# Wilssen_core_v0_207a.net
KiCad netlist of a schematic drawn in EAGLE
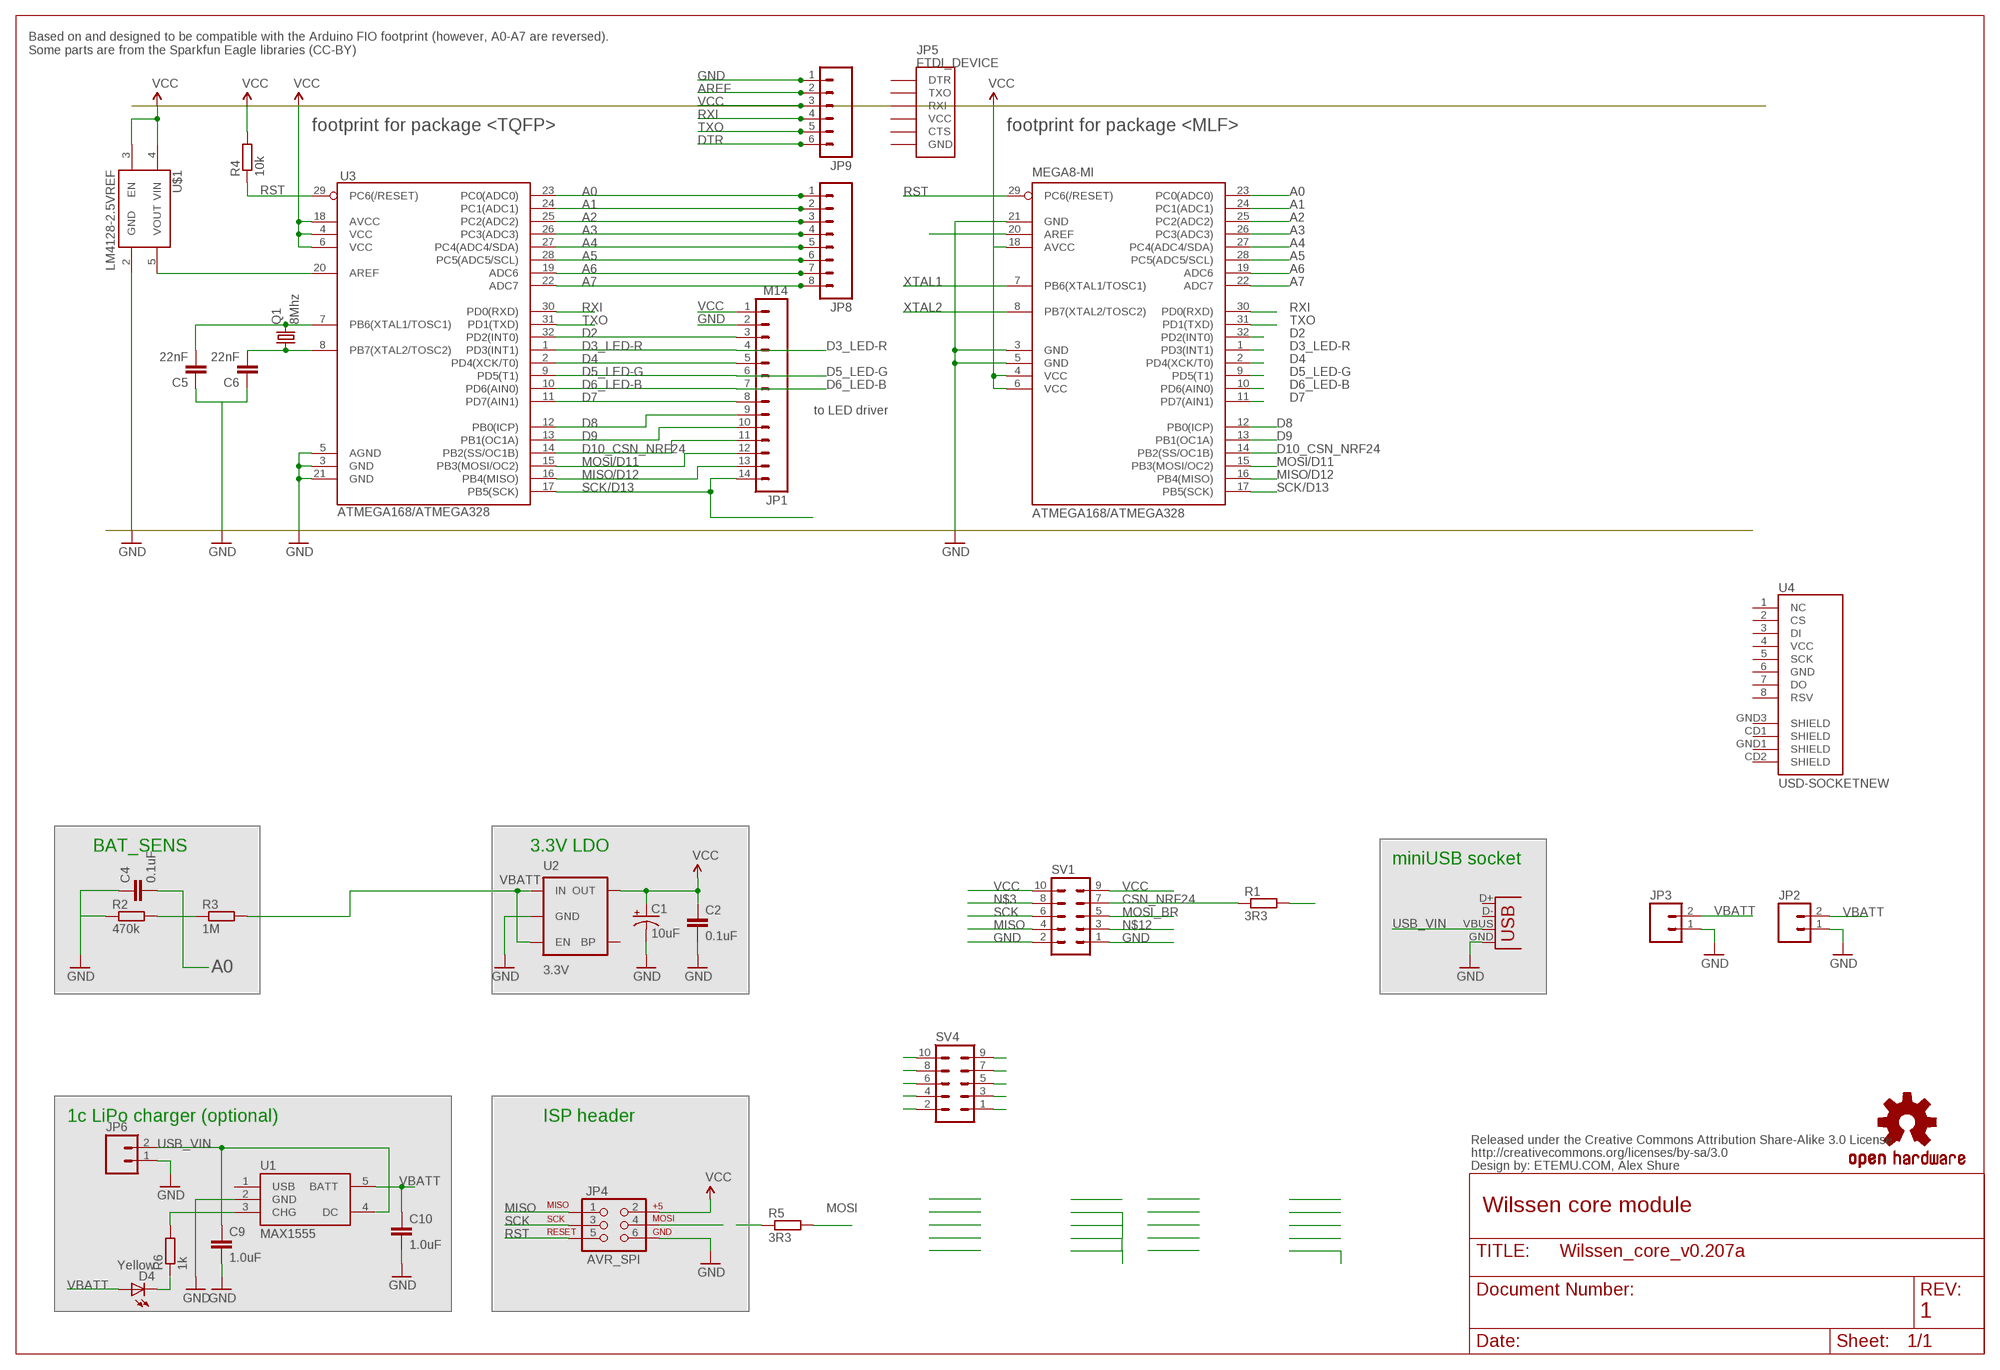
[diagram p0: schematic, sheet 1, part 1 of 2]
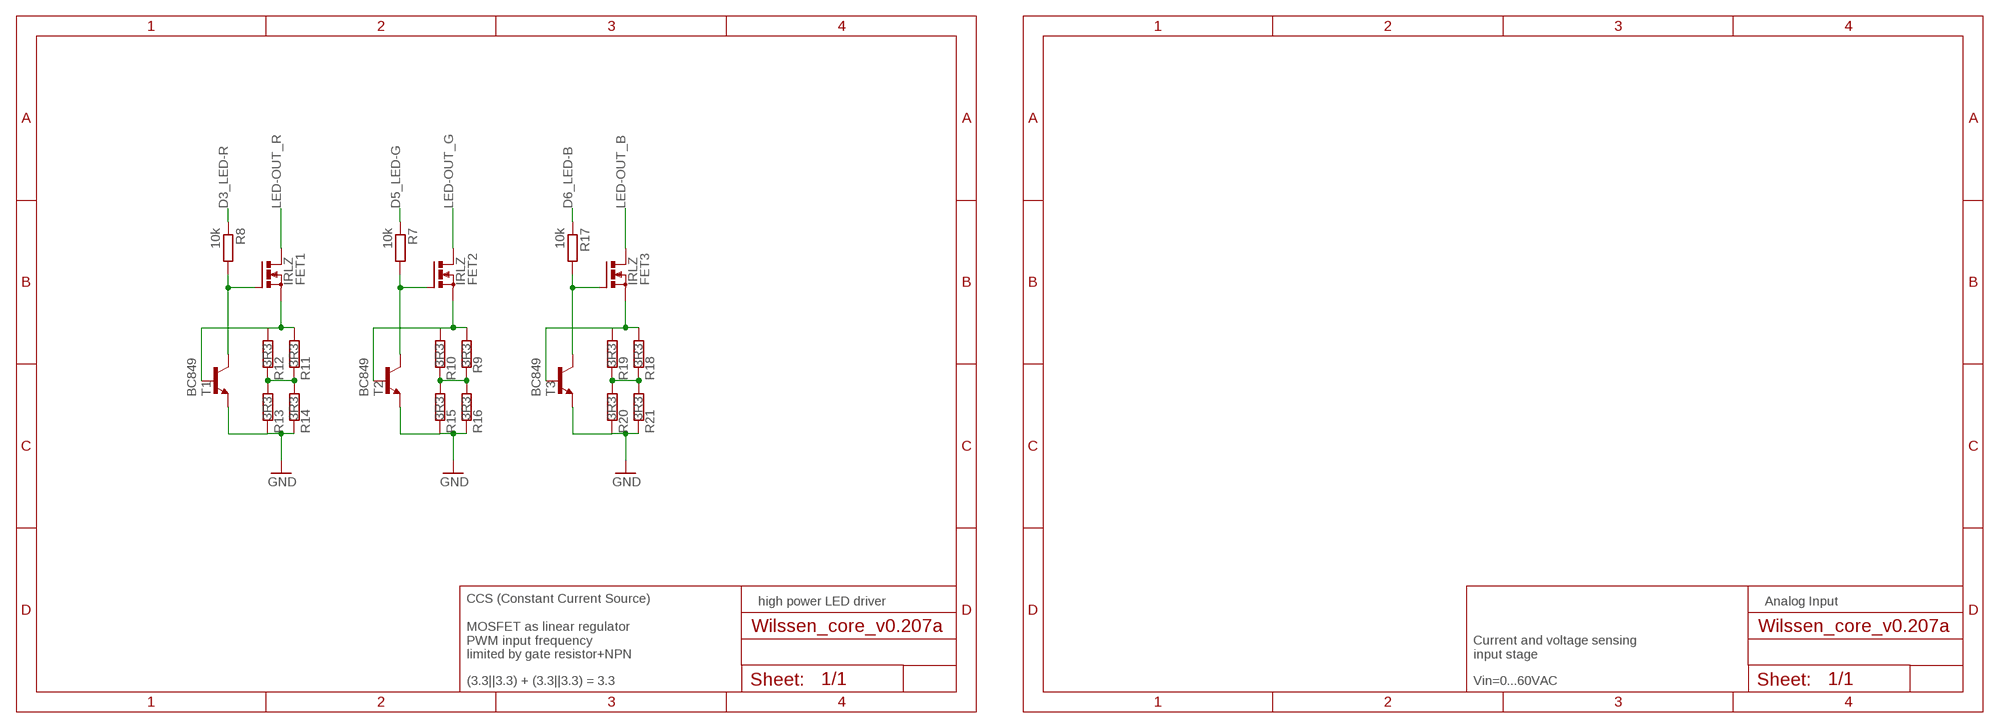
[diagram p1: schematic, sheet 1, part 2 of 2]

(export (version "E")
  (design (tool "Eeschema 10.0.6"))
  (components
    (comp (ref "ATMEGA168/ATMEGA328")
      (value "MEGA8-MI")
      (footprint "eagle-import:MLF32")
      (fields (field (name "MPN") "ATMEGA88PA-MU"))
      (libsource (lib "eagle-import") (part "MEGA8-MI"))
    )
    (comp (ref "C1")
      (value "10uF")
      (footprint "eagle-import:EIA3216")
      (libsource (lib "eagle-import") (part "CAP_POL1206"))
    )
    (comp (ref "C2")
      (value "0.1uF")
      (footprint "eagle-import:0805")
      (libsource (lib "eagle-import") (part "CAP0805"))
    )
    (comp (ref "C4")
      (value "0.1uF")
      (footprint "eagle-import:0805")
      (libsource (lib "eagle-import") (part "CAP0805"))
    )
    (comp (ref "C5")
      (value "22nF")
      (footprint "eagle-import:0805")
      (libsource (lib "eagle-import") (part "CAP0805"))
    )
    (comp (ref "C6")
      (value "22nF")
      (footprint "eagle-import:0805")
      (libsource (lib "eagle-import") (part "CAP0805"))
    )
    (comp (ref "C9")
      (value "1.0uF")
      (footprint "eagle-import:0805")
      (libsource (lib "eagle-import") (part "CAP0805"))
    )
    (comp (ref "C10")
      (value "1.0uF")
      (footprint "eagle-import:0805")
      (libsource (lib "eagle-import") (part "CAP0805"))
    )
    (comp (ref "CC_TEXT1")
      (value "CREATIVE_COMMONS")
      (footprint "eagle-import:CREATIVE_COMMONS")
      (libsource (lib "eagle-import") (part "CREATIVE_COMMONS"))
    )
    (comp (ref "D4")
      (value "Yellow")
      (footprint "eagle-import:LED-0603")
      (libsource (lib "eagle-import") (part "LED0603"))
    )
    (comp (ref "FET1")
      (value "IRLZ")
      (footprint "eagle-import:TO220BV")
      (libsource (lib "eagle-import") (part "PMOSFET_NTO220BV"))
    )
    (comp (ref "FET2")
      (value "IRLZ")
      (footprint "eagle-import:TO220BV")
      (libsource (lib "eagle-import") (part "PMOSFET_NTO220BV"))
    )
    (comp (ref "FET3")
      (value "IRLZ")
      (footprint "eagle-import:TO220BV")
      (libsource (lib "eagle-import") (part "PMOSFET_NTO220BV"))
    )
    (comp (ref "JP1")
      (value "M14")
      (footprint "eagle-import:1X14")
      (libsource (lib "eagle-import") (part "M14"))
    )
    (comp (ref "JP2")
      (value "M02PTH")
      (footprint "eagle-import:1X02")
      (libsource (lib "eagle-import") (part "M02PTH"))
    )
    (comp (ref "JP3")
      (value "M02-JST-2MM-SMT")
      (footprint "eagle-import:S2B-PH")
      (libsource (lib "eagle-import") (part "M02-JST-2MM-SMT"))
    )
    (comp (ref "JP4")
      (value "AVR_SPI")
      (footprint "eagle-import:2X3")
      (libsource (lib "eagle-import") (part "AVR_SPI_PRG_6PTH"))
    )
    (comp (ref "JP5")
      (value "FTDI_DEVICE")
      (footprint "eagle-import:FTDI_DEVICE_SIDE")
      (libsource (lib "eagle-import") (part "FTDI_DEVICE"))
    )
    (comp (ref "JP6")
      (value "M02PTH")
      (footprint "eagle-import:1X02")
      (libsource (lib "eagle-import") (part "M02PTH"))
    )
    (comp (ref "JP8")
      (value "M081X08")
      (footprint "eagle-import:1X08")
      (libsource (lib "eagle-import") (part "M081X08"))
    )
    (comp (ref "JP9")
      (value "M06SIP")
      (footprint "eagle-import:1X06")
      (libsource (lib "eagle-import") (part "M06SIP"))
    )
    (comp (ref "LOGO1")
      (value "OSHW-LOGOS")
      (footprint "eagle-import:OSHW-LOGO-S")
      (libsource (lib "eagle-import") (part "OSHW-LOGOS"))
    )
    (comp (ref "Q1")
      (value "8Mhz")
      (footprint "eagle-import:SM49")
      (libsource (lib "eagle-import") (part "CRYSTALSM49"))
    )
    (comp (ref "R1")
      (value "3R3")
      (footprint "eagle-import:R1206")
      (libsource (lib "eagle-import") (part "R-EU_R1206"))
    )
    (comp (ref "R2")
      (value "470k")
      (footprint "eagle-import:R0805")
      (libsource (lib "eagle-import") (part "R-EU_R0805"))
    )
    (comp (ref "R3")
      (value "1M")
      (footprint "eagle-import:R0805")
      (libsource (lib "eagle-import") (part "R-EU_R0805"))
    )
    (comp (ref "R4")
      (value "10k")
      (footprint "eagle-import:R0805")
      (libsource (lib "eagle-import") (part "R-EU_R0805"))
    )
    (comp (ref "R5")
      (value "3R3")
      (footprint "eagle-import:R1206")
      (libsource (lib "eagle-import") (part "R-EU_R1206"))
    )
    (comp (ref "R6")
      (value "1k")
      (footprint "eagle-import:R0805")
      (libsource (lib "eagle-import") (part "R-EU_R0805"))
    )
    (comp (ref "R7")
      (value "10k")
      (footprint "eagle-import:R0805")
      (libsource (lib "eagle-import") (part "resistor_R-EU_R0805"))
    )
    (comp (ref "R8")
      (value "10k")
      (footprint "eagle-import:R0805")
      (libsource (lib "eagle-import") (part "resistor_R-EU_R0805"))
    )
    (comp (ref "R9")
      (value "3R3")
      (footprint "eagle-import:R1206")
      (libsource (lib "eagle-import") (part "resistor_R-EU_R1206"))
    )
    (comp (ref "R10")
      (value "3R3")
      (footprint "eagle-import:R1206")
      (libsource (lib "eagle-import") (part "resistor_R-EU_R1206"))
    )
    (comp (ref "R11")
      (value "3R3")
      (footprint "eagle-import:R1206")
      (libsource (lib "eagle-import") (part "resistor_R-EU_R1206"))
    )
    (comp (ref "R12")
      (value "3R3")
      (footprint "eagle-import:R1206")
      (libsource (lib "eagle-import") (part "resistor_R-EU_R1206"))
    )
    (comp (ref "R13")
      (value "3R3")
      (footprint "eagle-import:R1206")
      (libsource (lib "eagle-import") (part "resistor_R-EU_R1206"))
    )
    (comp (ref "R14")
      (value "3R3")
      (footprint "eagle-import:R1206")
      (libsource (lib "eagle-import") (part "resistor_R-EU_R1206"))
    )
    (comp (ref "R15")
      (value "3R3")
      (footprint "eagle-import:R1206")
      (libsource (lib "eagle-import") (part "resistor_R-EU_R1206"))
    )
    (comp (ref "R16")
      (value "3R3")
      (footprint "eagle-import:R1206")
      (libsource (lib "eagle-import") (part "resistor_R-EU_R1206"))
    )
    (comp (ref "R17")
      (value "10k")
      (footprint "eagle-import:R0805")
      (libsource (lib "eagle-import") (part "resistor_R-EU_R0805"))
    )
    (comp (ref "R18")
      (value "3R3")
      (footprint "eagle-import:R1206")
      (libsource (lib "eagle-import") (part "resistor_R-EU_R1206"))
    )
    (comp (ref "R19")
      (value "3R3")
      (footprint "eagle-import:R1206")
      (libsource (lib "eagle-import") (part "resistor_R-EU_R1206"))
    )
    (comp (ref "R20")
      (value "3R3")
      (footprint "eagle-import:R1206")
      (libsource (lib "eagle-import") (part "resistor_R-EU_R1206"))
    )
    (comp (ref "R21")
      (value "3R3")
      (footprint "eagle-import:R1206")
      (libsource (lib "eagle-import") (part "resistor_R-EU_R1206"))
    )
    (comp (ref "SV1")
      (value "MA05-2")
      (footprint "eagle-import:MA05-2")
      (libsource (lib "eagle-import") (part "MA05-2"))
    )
    (comp (ref "SV4")
      (value "MA05-2")
      (footprint "eagle-import:MA05-2")
      (libsource (lib "eagle-import") (part "MA05-2"))
    )
    (comp (ref "T1")
      (value "BC849")
      (footprint "eagle-import:SOT23")
      (libsource (lib "eagle-import") (part "BC849"))
    )
    (comp (ref "T2")
      (value "BC849")
      (footprint "eagle-import:SOT23")
      (libsource (lib "eagle-import") (part "BC849"))
    )
    (comp (ref "T3")
      (value "BC849")
      (footprint "eagle-import:SOT23")
      (libsource (lib "eagle-import") (part "BC849"))
    )
    (comp (ref "U$1")
      (value "LM4128-2.5VREF")
      (footprint "eagle-import:SOT23-5")
      (libsource (lib "eagle-import") (part "LM4128-2.5VREF"))
    )
    (comp (ref "U1")
      (value "MAX1555")
      (footprint "eagle-import:SOT23-5")
      (libsource (lib "eagle-import") (part "MAX1555"))
    )
    (comp (ref "U2")
      (value "3.3V")
      (footprint "eagle-import:SOT23-5")
      (libsource (lib "eagle-import") (part "V_REG_LDOSMD"))
    )
    (comp (ref "U3")
      (value "ATMEGA168/ATMEGA328")
      (footprint "eagle-import:TQFP32-08")
      (libsource (lib "eagle-import") (part "ATMEGA168"))
    )
    (comp (ref "U4")
      (value "USD-SOCKETNEW")
      (footprint "eagle-import:MICRO-SD-SOCKET-PP")
      (libsource (lib "eagle-import") (part "USD-SOCKETNEW"))
    )
    (comp (ref "X1")
      (value "USBSMD")
      (footprint "eagle-import:USB-MINIB")
      (libsource (lib "eagle-import") (part "USBSMD"))
    )
  )
  (nets
    (net (code "1") (name "/A0") (class "Default")
      (node (ref "ATMEGA168/ATMEGA328") (pin "23") (pinfunction "PC0(ADC0)_23") (pintype "bidirectional"))
      (node (ref "C4") (pin "2") (pinfunction "2_2") (pintype "passive"))
      (node (ref "JP8") (pin "1") (pinfunction "1_1") (pintype "passive"))
      (node (ref "R2") (pin "2") (pinfunction "2_2") (pintype "passive"))
      (node (ref "R3") (pin "1") (pinfunction "1_1") (pintype "passive"))
      (node (ref "U3") (pin "23") (pinfunction "PC0(ADC0)_23") (pintype "bidirectional"))
    )
    (net (code "2") (name "/A1") (class "Default")
      (node (ref "ATMEGA168/ATMEGA328") (pin "24") (pinfunction "PC1(ADC1)_24") (pintype "bidirectional"))
      (node (ref "JP8") (pin "2") (pinfunction "2_2") (pintype "passive"))
      (node (ref "U3") (pin "24") (pinfunction "PC1(ADC1)_24") (pintype "bidirectional"))
    )
    (net (code "3") (name "/A2") (class "Default")
      (node (ref "ATMEGA168/ATMEGA328") (pin "25") (pinfunction "PC2(ADC2)_25") (pintype "bidirectional"))
      (node (ref "JP8") (pin "3") (pinfunction "3_3") (pintype "passive"))
      (node (ref "U3") (pin "25") (pinfunction "PC2(ADC2)_25") (pintype "bidirectional"))
    )
    (net (code "4") (name "/A3") (class "Default")
      (node (ref "ATMEGA168/ATMEGA328") (pin "26") (pinfunction "PC3(ADC3)_26") (pintype "bidirectional"))
      (node (ref "JP8") (pin "4") (pinfunction "4_4") (pintype "passive"))
      (node (ref "U3") (pin "26") (pinfunction "PC3(ADC3)_26") (pintype "bidirectional"))
    )
    (net (code "5") (name "/A4") (class "Default")
      (node (ref "ATMEGA168/ATMEGA328") (pin "27") (pinfunction "PC4(ADC4/SDA)_27") (pintype "bidirectional"))
      (node (ref "JP8") (pin "5") (pinfunction "5_5") (pintype "passive"))
      (node (ref "U3") (pin "27") (pinfunction "PC4(ADC4/SDA)_27") (pintype "bidirectional"))
    )
    (net (code "6") (name "/A5") (class "Default")
      (node (ref "ATMEGA168/ATMEGA328") (pin "28") (pinfunction "PC5(ADC5/SCL)_28") (pintype "bidirectional"))
      (node (ref "JP8") (pin "6") (pinfunction "6_6") (pintype "passive"))
      (node (ref "U3") (pin "28") (pinfunction "PC5(ADC5/SCL)_28") (pintype "bidirectional"))
    )
    (net (code "7") (name "/A6") (class "Default")
      (node (ref "ATMEGA168/ATMEGA328") (pin "19") (pinfunction "ADC6_19") (pintype "bidirectional"))
      (node (ref "JP8") (pin "7") (pinfunction "7_7") (pintype "passive"))
      (node (ref "U3") (pin "19") (pinfunction "ADC6_19") (pintype "bidirectional"))
    )
    (net (code "8") (name "/A7") (class "Default")
      (node (ref "ATMEGA168/ATMEGA328") (pin "22") (pinfunction "ADC7_22") (pintype "bidirectional"))
      (node (ref "JP8") (pin "8") (pinfunction "8_8") (pintype "passive"))
      (node (ref "U3") (pin "22") (pinfunction "ADC7_22") (pintype "bidirectional"))
    )
    (net (code "9") (name "/AREF") (class "Default")
      (node (ref "ATMEGA168/ATMEGA328") (pin "20") (pinfunction "AREF_20") (pintype "passive"))
      (node (ref "JP9") (pin "2") (pinfunction "2_2") (pintype "passive"))
      (node (ref "U$1") (pin "5") (pinfunction "VOUT_5") (pintype "bidirectional"))
      (node (ref "U3") (pin "20") (pinfunction "AREF_20") (pintype "bidirectional"))
    )
    (net (code "10") (name "/CSN") (class "Default")
      (node (ref "SV4") (pin "8") (pinfunction "8_8") (pintype "passive"))
    )
    (net (code "11") (name "/CSN_NRF24") (class "Default")
      (node (ref "R1") (pin "1") (pinfunction "1_1") (pintype "passive"))
      (node (ref "SV1") (pin "7") (pinfunction "7_7") (pintype "passive"))
    )
    (net (code "12") (name "/D2") (class "Default")
      (node (ref "ATMEGA168/ATMEGA328") (pin "32") (pinfunction "PD2(INT0)_32") (pintype "bidirectional"))
      (node (ref "JP1") (pin "3") (pinfunction "3_3") (pintype "passive"))
      (node (ref "U3") (pin "32") (pinfunction "PD2(INT0)_32") (pintype "bidirectional"))
    )
    (net (code "13") (name "/D3_LED-R") (class "Default")
      (node (ref "ATMEGA168/ATMEGA328") (pin "1") (pinfunction "PD3(INT1)_1") (pintype "bidirectional"))
      (node (ref "JP1") (pin "4") (pinfunction "4_4") (pintype "passive"))
      (node (ref "R8") (pin "1") (pinfunction "1_1") (pintype "passive"))
      (node (ref "U3") (pin "1") (pinfunction "PD3(INT1)_1") (pintype "bidirectional"))
    )
    (net (code "14") (name "/D4") (class "Default")
      (node (ref "ATMEGA168/ATMEGA328") (pin "2") (pinfunction "PD4(XCK/T0)_2") (pintype "bidirectional"))
      (node (ref "JP1") (pin "5") (pinfunction "5_5") (pintype "passive"))
      (node (ref "U3") (pin "2") (pinfunction "PD4(XCK/T0)_2") (pintype "bidirectional"))
    )
    (net (code "15") (name "/D5_LED-G") (class "Default")
      (node (ref "ATMEGA168/ATMEGA328") (pin "9") (pinfunction "PD5(T1)_9") (pintype "bidirectional"))
      (node (ref "JP1") (pin "6") (pinfunction "6_6") (pintype "passive"))
      (node (ref "R7") (pin "1") (pinfunction "1_1") (pintype "passive"))
      (node (ref "U3") (pin "9") (pinfunction "PD5(T1)_9") (pintype "bidirectional"))
    )
    (net (code "16") (name "/D6_LED-B") (class "Default")
      (node (ref "ATMEGA168/ATMEGA328") (pin "10") (pinfunction "PD6(AIN0)_10") (pintype "bidirectional"))
      (node (ref "JP1") (pin "7") (pinfunction "7_7") (pintype "passive"))
      (node (ref "R17") (pin "1") (pinfunction "1_1") (pintype "passive"))
      (node (ref "U3") (pin "10") (pinfunction "PD6(AIN0)_10") (pintype "bidirectional"))
    )
    (net (code "17") (name "/D7") (class "Default")
      (node (ref "ATMEGA168/ATMEGA328") (pin "11") (pinfunction "PD7(AIN1)_11") (pintype "bidirectional"))
      (node (ref "JP1") (pin "8") (pinfunction "8_8") (pintype "passive"))
      (node (ref "U3") (pin "11") (pinfunction "PD7(AIN1)_11") (pintype "bidirectional"))
    )
    (net (code "18") (name "/D8") (class "Default")
      (node (ref "ATMEGA168/ATMEGA328") (pin "12") (pinfunction "PB0(ICP)_12") (pintype "bidirectional"))
      (node (ref "JP1") (pin "9") (pinfunction "9_9") (pintype "passive"))
      (node (ref "U3") (pin "12") (pinfunction "PB0(ICP)_12") (pintype "bidirectional"))
    )
    (net (code "19") (name "/D9") (class "Default")
      (node (ref "ATMEGA168/ATMEGA328") (pin "13") (pinfunction "PB1(OC1A)_13") (pintype "bidirectional"))
      (node (ref "JP1") (pin "10") (pinfunction "10_10") (pintype "passive"))
      (node (ref "U3") (pin "13") (pinfunction "PB1(OC1A)_13") (pintype "bidirectional"))
    )
    (net (code "20") (name "/D10_CSN_NRF24") (class "Default")
      (node (ref "ATMEGA168/ATMEGA328") (pin "14") (pinfunction "PB2(SS/OC1B)_14") (pintype "bidirectional"))
      (node (ref "JP1") (pin "11") (pinfunction "11_11") (pintype "passive"))
      (node (ref "R1") (pin "2") (pinfunction "2_2") (pintype "passive"))
      (node (ref "U3") (pin "14") (pinfunction "PB2(SS/OC1B)_14") (pintype "bidirectional"))
    )
    (net (code "21") (name "/DTR") (class "Default")
      (node (ref "JP9") (pin "6") (pinfunction "6_6") (pintype "passive"))
    )
    (net (code "22") (name "/LED-OUT_B") (class "Default")
      (node (ref "FET3") (pin "D") (pinfunction "D_D") (pintype "passive"))
    )
    (net (code "23") (name "/LED-OUT_G") (class "Default")
      (node (ref "FET2") (pin "D") (pinfunction "D_D") (pintype "passive"))
    )
    (net (code "24") (name "/LED-OUT_R") (class "Default")
      (node (ref "FET1") (pin "D") (pinfunction "D_D") (pintype "passive"))
    )
    (net (code "25") (name "/MISO") (class "Default")
      (node (ref "ATMEGA168/ATMEGA328") (pin "16") (pinfunction "PB4(MISO)_16") (pintype "bidirectional"))
      (node (ref "JP1") (pin "13") (pinfunction "13_13") (pintype "passive"))
      (node (ref "JP4") (pin "1") (pinfunction "1_1") (pintype "passive"))
      (node (ref "SV1") (pin "4") (pinfunction "4_4") (pintype "passive"))
      (node (ref "SV4") (pin "2") (pinfunction "2_2") (pintype "passive"))
      (node (ref "U3") (pin "16") (pinfunction "PB4(MISO)_16") (pintype "bidirectional"))
    )
    (net (code "26") (name "/MOSI") (class "Default")
      (node (ref "ATMEGA168/ATMEGA328") (pin "15") (pinfunction "PB3(MOSI/OC2)_15") (pintype "bidirectional"))
      (node (ref "JP1") (pin "12") (pinfunction "12_12") (pintype "passive"))
      (node (ref "JP4") (pin "4") (pinfunction "4_4") (pintype "passive"))
      (node (ref "R5") (pin "2") (pinfunction "2_2") (pintype "passive"))
      (node (ref "SV4") (pin "10") (pinfunction "10_10") (pintype "passive"))
      (node (ref "U3") (pin "15") (pinfunction "PB3(MOSI/OC2)_15") (pintype "bidirectional"))
    )
    (net (code "27") (name "/MOSI_BR") (class "Default")
      (node (ref "SV1") (pin "5") (pinfunction "5_5") (pintype "passive"))
    )
    (net (code "28") (name "/N$3") (class "Default")
      (node (ref "SV1") (pin "8") (pinfunction "8_8") (pintype "passive"))
    )
    (net (code "29") (name "/N$12") (class "Default")
      (node (ref "SV1") (pin "3") (pinfunction "3_3") (pintype "passive"))
    )
    (net (code "30") (name "/RST") (class "Default")
      (node (ref "ATMEGA168/ATMEGA328") (pin "29") (pinfunction "PC6(/RESET)_29") (pintype "bidirectional"))
      (node (ref "JP4") (pin "5") (pinfunction "5_5") (pintype "passive"))
      (node (ref "R4") (pin "1") (pinfunction "1_1") (pintype "passive"))
      (node (ref "SV4") (pin "6") (pinfunction "6_6") (pintype "passive"))
      (node (ref "U3") (pin "29") (pinfunction "PC6(/RESET)_29") (pintype "bidirectional"))
    )
    (net (code "31") (name "/RXI") (class "Default")
      (node (ref "ATMEGA168/ATMEGA328") (pin "30") (pinfunction "PD0(RXD)_30") (pintype "bidirectional"))
      (node (ref "JP9") (pin "4") (pinfunction "4_4") (pintype "passive"))
      (node (ref "U3") (pin "30") (pinfunction "PD0(RXD)_30") (pintype "bidirectional"))
    )
    (net (code "32") (name "/SCK") (class "Default")
      (node (ref "ATMEGA168/ATMEGA328") (pin "17") (pinfunction "PB5(SCK)_17") (pintype "bidirectional"))
      (node (ref "JP1") (pin "14") (pinfunction "14_14") (pintype "passive"))
      (node (ref "JP4") (pin "3") (pinfunction "3_3") (pintype "passive"))
      (node (ref "SV1") (pin "6") (pinfunction "6_6") (pintype "passive"))
      (node (ref "SV4") (pin "4") (pinfunction "4_4") (pintype "passive"))
      (node (ref "U3") (pin "17") (pinfunction "PB5(SCK)_17") (pintype "bidirectional"))
    )
    (net (code "33") (name "/TXO") (class "Default")
      (node (ref "ATMEGA168/ATMEGA328") (pin "31") (pinfunction "PD1(TXD)_31") (pintype "bidirectional"))
      (node (ref "JP9") (pin "5") (pinfunction "5_5") (pintype "passive"))
      (node (ref "U3") (pin "31") (pinfunction "PD1(TXD)_31") (pintype "bidirectional"))
    )
    (net (code "34") (name "/USB_VIN") (class "Default")
      (node (ref "C9") (pin "1") (pinfunction "1_1") (pintype "passive"))
      (node (ref "JP6") (pin "2") (pinfunction "2_2") (pintype "passive"))
      (node (ref "U1") (pin "4") (pinfunction "DC_4") (pintype "bidirectional"))
      (node (ref "X1") (pin "VBUS") (pinfunction "VBUS_VBUS") (pintype "bidirectional"))
    )
    (net (code "35") (name "/VBATT") (class "Default")
      (node (ref "C10") (pin "1") (pinfunction "1_1") (pintype "passive"))
      (node (ref "D4") (pin "A") (pinfunction "A_A") (pintype "passive"))
      (node (ref "JP2") (pin "2") (pinfunction "2_2") (pintype "passive"))
      (node (ref "JP3") (pin "2") (pinfunction "2_2") (pintype "passive"))
      (node (ref "R3") (pin "2") (pinfunction "2_2") (pintype "passive"))
      (node (ref "U1") (pin "5") (pinfunction "BATT_5") (pintype "bidirectional"))
      (node (ref "U2") (pin "1") (pinfunction "IN_1") (pintype "input"))
      (node (ref "U2") (pin "3") (pinfunction "EN_3") (pintype "input"))
    )
    (net (code "36") (name "/XTAL1") (class "Default")
      (node (ref "ATMEGA168/ATMEGA328") (pin "7") (pinfunction "PB6(XTAL1/TOSC1)_7") (pintype "bidirectional"))
      (node (ref "C5") (pin "2") (pinfunction "2_2") (pintype "passive"))
      (node (ref "Q1") (pin "2") (pinfunction "2_2") (pintype "passive"))
      (node (ref "U3") (pin "7") (pinfunction "PB6(XTAL1/TOSC1)_7") (pintype "bidirectional"))
    )
    (net (code "37") (name "/XTAL2") (class "Default")
      (node (ref "ATMEGA168/ATMEGA328") (pin "8") (pinfunction "PB7(XTAL2/TOSC2)_8") (pintype "bidirectional"))
      (node (ref "C6") (pin "2") (pinfunction "2_2") (pintype "passive"))
      (node (ref "Q1") (pin "1") (pinfunction "1_1") (pintype "passive"))
      (node (ref "U3") (pin "8") (pinfunction "PB7(XTAL2/TOSC2)_8") (pintype "bidirectional"))
    )
    (net (code "38") (name "GND") (class "Default")
      (node (ref "ATMEGA168/ATMEGA328") (pin "21") (pinfunction "GND_21") (pintype "power_in"))
      (node (ref "ATMEGA168/ATMEGA328") (pin "3") (pinfunction "GND_3") (pintype "power_in"))
      (node (ref "ATMEGA168/ATMEGA328") (pin "5") (pinfunction "GND_5") (pintype "power_in"))
      (node (ref "C1") (pin "C") (pinfunction "-_C") (pintype "passive"))
      (node (ref "C10") (pin "2") (pinfunction "2_2") (pintype "passive"))
      (node (ref "C2") (pin "2") (pinfunction "2_2") (pintype "passive"))
      (node (ref "C4") (pin "1") (pinfunction "1_1") (pintype "passive"))
      (node (ref "C5") (pin "1") (pinfunction "1_1") (pintype "passive"))
      (node (ref "C6") (pin "1") (pinfunction "1_1") (pintype "passive"))
      (node (ref "C9") (pin "2") (pinfunction "2_2") (pintype "passive"))
      (node (ref "JP1") (pin "2") (pinfunction "2_2") (pintype "passive"))
      (node (ref "JP2") (pin "1") (pinfunction "1_1") (pintype "passive"))
      (node (ref "JP3") (pin "1") (pinfunction "1_1") (pintype "passive"))
      (node (ref "JP4") (pin "6") (pinfunction "6_6") (pintype "passive"))
      (node (ref "JP6") (pin "1") (pinfunction "1_1") (pintype "passive"))
      (node (ref "JP9") (pin "1") (pinfunction "1_1") (pintype "passive"))
      (node (ref "R13") (pin "2") (pinfunction "2_2") (pintype "passive"))
      (node (ref "R14") (pin "2") (pinfunction "2_2") (pintype "passive"))
      (node (ref "R15") (pin "2") (pinfunction "2_2") (pintype "passive"))
      (node (ref "R16") (pin "2") (pinfunction "2_2") (pintype "passive"))
      (node (ref "R2") (pin "1") (pinfunction "1_1") (pintype "passive"))
      (node (ref "R20") (pin "2") (pinfunction "2_2") (pintype "passive"))
      (node (ref "R21") (pin "2") (pinfunction "2_2") (pintype "passive"))
      (node (ref "SV1") (pin "1") (pinfunction "1_1") (pintype "passive"))
      (node (ref "SV1") (pin "2") (pinfunction "2_2") (pintype "passive"))
      (node (ref "SV4") (pin "1") (pinfunction "1_1") (pintype "passive"))
      (node (ref "SV4") (pin "3") (pinfunction "3_3") (pintype "passive"))
      (node (ref "SV4") (pin "5") (pinfunction "5_5") (pintype "passive"))
      (node (ref "SV4") (pin "7") (pinfunction "7_7") (pintype "passive"))
      (node (ref "T1") (pin "2") (pinfunction "E_2") (pintype "passive"))
      (node (ref "T2") (pin "2") (pinfunction "E_2") (pintype "passive"))
      (node (ref "T3") (pin "2") (pinfunction "E_2") (pintype "passive"))
      (node (ref "U$1") (pin "2") (pinfunction "GND_2") (pintype "bidirectional"))
      (node (ref "U1") (pin "2") (pinfunction "GND_2") (pintype "bidirectional"))
      (node (ref "U2") (pin "2") (pinfunction "GND_2") (pintype "input"))
      (node (ref "U3") (pin "21") (pinfunction "GND_21") (pintype "bidirectional"))
      (node (ref "U3") (pin "3") (pinfunction "GND_3") (pintype "bidirectional"))
      (node (ref "U3") (pin "5") (pinfunction "AGND_5") (pintype "bidirectional"))
      (node (ref "X1") (pin "GND") (pinfunction "GND_GND") (pintype "bidirectional"))
    )
    (net (code "39") (name "Net-(D4-PadC)") (class "Default")
      (node (ref "D4") (pin "C") (pinfunction "C_C") (pintype "passive"))
      (node (ref "R6") (pin "1") (pinfunction "1_1") (pintype "passive"))
    )
    (net (code "40") (name "Net-(R10-Pad2)") (class "Default")
      (node (ref "R10") (pin "2") (pinfunction "2_2") (pintype "passive"))
      (node (ref "R15") (pin "1") (pinfunction "1_1") (pintype "passive"))
      (node (ref "R16") (pin "1") (pinfunction "1_1") (pintype "passive"))
      (node (ref "R9") (pin "2") (pinfunction "2_2") (pintype "passive"))
    )
    (net (code "41") (name "Net-(R11-Pad2)") (class "Default")
      (node (ref "R11") (pin "2") (pinfunction "2_2") (pintype "passive"))
      (node (ref "R12") (pin "2") (pinfunction "2_2") (pintype "passive"))
      (node (ref "R13") (pin "1") (pinfunction "1_1") (pintype "passive"))
      (node (ref "R14") (pin "1") (pinfunction "1_1") (pintype "passive"))
    )
    (net (code "42") (name "Net-(R18-Pad2)") (class "Default")
      (node (ref "R18") (pin "2") (pinfunction "2_2") (pintype "passive"))
      (node (ref "R19") (pin "2") (pinfunction "2_2") (pintype "passive"))
      (node (ref "R20") (pin "1") (pinfunction "1_1") (pintype "passive"))
      (node (ref "R21") (pin "1") (pinfunction "1_1") (pintype "passive"))
    )
    (net (code "43") (name "Net-(T1-B)") (class "Default")
      (node (ref "FET1") (pin "S") (pinfunction "S_S") (pintype "passive"))
      (node (ref "R11") (pin "1") (pinfunction "1_1") (pintype "passive"))
      (node (ref "R12") (pin "1") (pinfunction "1_1") (pintype "passive"))
      (node (ref "T1") (pin "1") (pinfunction "B_1") (pintype "passive"))
    )
    (net (code "44") (name "Net-(T1-C)") (class "Default")
      (node (ref "FET1") (pin "G") (pinfunction "G_G") (pintype "passive"))
      (node (ref "R8") (pin "2") (pinfunction "2_2") (pintype "passive"))
      (node (ref "T1") (pin "3") (pinfunction "C_3") (pintype "passive"))
    )
    (net (code "45") (name "Net-(T2-B)") (class "Default")
      (node (ref "FET2") (pin "S") (pinfunction "S_S") (pintype "passive"))
      (node (ref "R10") (pin "1") (pinfunction "1_1") (pintype "passive"))
      (node (ref "R9") (pin "1") (pinfunction "1_1") (pintype "passive"))
      (node (ref "T2") (pin "1") (pinfunction "B_1") (pintype "passive"))
    )
    (net (code "46") (name "Net-(T2-C)") (class "Default")
      (node (ref "FET2") (pin "G") (pinfunction "G_G") (pintype "passive"))
      (node (ref "R7") (pin "2") (pinfunction "2_2") (pintype "passive"))
      (node (ref "T2") (pin "3") (pinfunction "C_3") (pintype "passive"))
    )
    (net (code "47") (name "Net-(T3-B)") (class "Default")
      (node (ref "FET3") (pin "S") (pinfunction "S_S") (pintype "passive"))
      (node (ref "R18") (pin "1") (pinfunction "1_1") (pintype "passive"))
      (node (ref "R19") (pin "1") (pinfunction "1_1") (pintype "passive"))
      (node (ref "T3") (pin "1") (pinfunction "B_1") (pintype "passive"))
    )
    (net (code "48") (name "Net-(T3-C)") (class "Default")
      (node (ref "FET3") (pin "G") (pinfunction "G_G") (pintype "passive"))
      (node (ref "R17") (pin "2") (pinfunction "2_2") (pintype "passive"))
      (node (ref "T3") (pin "3") (pinfunction "C_3") (pintype "passive"))
    )
    (net (code "49") (name "Net-(U1-CHG)") (class "Default")
      (node (ref "R6") (pin "2") (pinfunction "2_2") (pintype "passive"))
      (node (ref "U1") (pin "3") (pinfunction "CHG_3") (pintype "bidirectional"))
    )
    (net (code "50") (name "VCC") (class "Default")
      (node (ref "ATMEGA168/ATMEGA328") (pin "18") (pinfunction "AVCC_18") (pintype "power_in"))
      (node (ref "ATMEGA168/ATMEGA328") (pin "4") (pinfunction "VCC_4") (pintype "power_in"))
      (node (ref "ATMEGA168/ATMEGA328") (pin "6") (pinfunction "VCC_6") (pintype "power_in"))
      (node (ref "C1") (pin "A") (pinfunction "+_A") (pintype "passive"))
      (node (ref "C2") (pin "1") (pinfunction "1_1") (pintype "passive"))
      (node (ref "JP1") (pin "1") (pinfunction "1_1") (pintype "passive"))
      (node (ref "JP4") (pin "2") (pinfunction "2_2") (pintype "passive"))
      (node (ref "JP9") (pin "3") (pinfunction "3_3") (pintype "passive"))
      (node (ref "R4") (pin "2") (pinfunction "2_2") (pintype "passive"))
      (node (ref "SV1") (pin "10") (pinfunction "10_10") (pintype "passive"))
      (node (ref "SV1") (pin "9") (pinfunction "9_9") (pintype "passive"))
      (node (ref "SV4") (pin "9") (pinfunction "9_9") (pintype "passive"))
      (node (ref "U$1") (pin "3") (pinfunction "EN_3") (pintype "bidirectional"))
      (node (ref "U$1") (pin "4") (pinfunction "VIN_4") (pintype "bidirectional"))
      (node (ref "U2") (pin "5") (pinfunction "OUT_5") (pintype "passive"))
      (node (ref "U3") (pin "18") (pinfunction "AVCC_18") (pintype "bidirectional"))
      (node (ref "U3") (pin "4") (pinfunction "VCC_4") (pintype "bidirectional"))
      (node (ref "U3") (pin "6") (pinfunction "VCC_6") (pintype "bidirectional"))
    )
    (net (code "51") (name "unconnected-(JP5-CTS-PadP$5)") (class "Default")
      (node (ref "JP5") (pin "P$5") (pinfunction "CTS_P$5") (pintype "bidirectional"))
    )
    (net (code "52") (name "unconnected-(JP5-DTR-PadP$1)") (class "Default")
      (node (ref "JP5") (pin "P$1") (pinfunction "DTR_P$1") (pintype "bidirectional"))
    )
    (net (code "53") (name "unconnected-(JP5-GND-PadP$6)") (class "Default")
      (node (ref "JP5") (pin "P$6") (pinfunction "GND_P$6") (pintype "bidirectional"))
    )
    (net (code "54") (name "unconnected-(JP5-RXI-PadP$3)") (class "Default")
      (node (ref "JP5") (pin "P$3") (pinfunction "RXI_P$3") (pintype "bidirectional"))
    )
    (net (code "55") (name "unconnected-(JP5-TXO-PadP$2)") (class "Default")
      (node (ref "JP5") (pin "P$2") (pinfunction "TXO_P$2") (pintype "bidirectional"))
    )
    (net (code "56") (name "unconnected-(JP5-VCC-PadP$4)") (class "Default")
      (node (ref "JP5") (pin "P$4") (pinfunction "VCC_P$4") (pintype "bidirectional"))
    )
    (net (code "57") (name "unconnected-(R5-Pad1)") (class "Default")
      (node (ref "R5") (pin "1") (pinfunction "1_1") (pintype "passive"))
    )
    (net (code "58") (name "unconnected-(U1-USB-Pad1)") (class "Default")
      (node (ref "U1") (pin "1") (pinfunction "USB_1") (pintype "bidirectional"))
    )
    (net (code "59") (name "unconnected-(U2-BP-Pad4)") (class "Default")
      (node (ref "U2") (pin "4") (pinfunction "BP_4") (pintype "input"))
    )
    (net (code "60") (name "unconnected-(U4-CS-Pad2)") (class "Default")
      (node (ref "U4") (pin "2") (pinfunction "CS_2") (pintype "bidirectional"))
    )
    (net (code "61") (name "unconnected-(U4-DI-Pad3)") (class "Default")
      (node (ref "U4") (pin "3") (pinfunction "DI_3") (pintype "bidirectional"))
    )
    (net (code "62") (name "unconnected-(U4-DO-Pad7)") (class "Default")
      (node (ref "U4") (pin "7") (pinfunction "DO_7") (pintype "bidirectional"))
    )
    (net (code "63") (name "unconnected-(U4-GND-Pad6)") (class "Default")
      (node (ref "U4") (pin "6") (pinfunction "GND_6") (pintype "bidirectional"))
    )
    (net (code "64") (name "unconnected-(U4-NC-Pad1)") (class "Default")
      (node (ref "U4") (pin "1") (pinfunction "NC_1") (pintype "bidirectional"))
    )
    (net (code "65") (name "unconnected-(U4-RSV-Pad8)") (class "Default")
      (node (ref "U4") (pin "8") (pinfunction "RSV_8") (pintype "bidirectional"))
    )
    (net (code "66") (name "unconnected-(U4-SCK-Pad5)") (class "Default")
      (node (ref "U4") (pin "5") (pinfunction "SCK_5") (pintype "bidirectional"))
    )
    (net (code "67") (name "unconnected-(U4-SHIELD-PadCD1)") (class "Default")
      (node (ref "U4") (pin "CD1") (pinfunction "SHIELD_CD1") (pintype "bidirectional"))
    )
    (net (code "68") (name "unconnected-(U4-SHIELD-PadCD2)") (class "Default")
      (node (ref "U4") (pin "CD2") (pinfunction "SHIELD_CD2") (pintype "bidirectional"))
    )
    (net (code "69") (name "unconnected-(U4-SHIELD-PadGND1)") (class "Default")
      (node (ref "U4") (pin "GND1") (pinfunction "SHIELD_GND1") (pintype "bidirectional"))
    )
    (net (code "70") (name "unconnected-(U4-SHIELD-PadGND3)") (class "Default")
      (node (ref "U4") (pin "GND3") (pinfunction "SHIELD_GND3") (pintype "bidirectional"))
    )
    (net (code "71") (name "unconnected-(U4-VCC-Pad4)") (class "Default")
      (node (ref "U4") (pin "4") (pinfunction "VCC_4") (pintype "bidirectional"))
    )
    (net (code "72") (name "unconnected-(X1-PadD+)") (class "Default")
      (node (ref "X1") (pin "D+") (pinfunction "D+_D+") (pintype "bidirectional"))
    )
    (net (code "73") (name "unconnected-(X1-PadD-)") (class "Default")
      (node (ref "X1") (pin "D-") (pinfunction "D-_D-") (pintype "bidirectional"))
    )
  )
)
